# ext_bootload_activation.net
KiCad netlist of a schematic drawn in Altium Designer
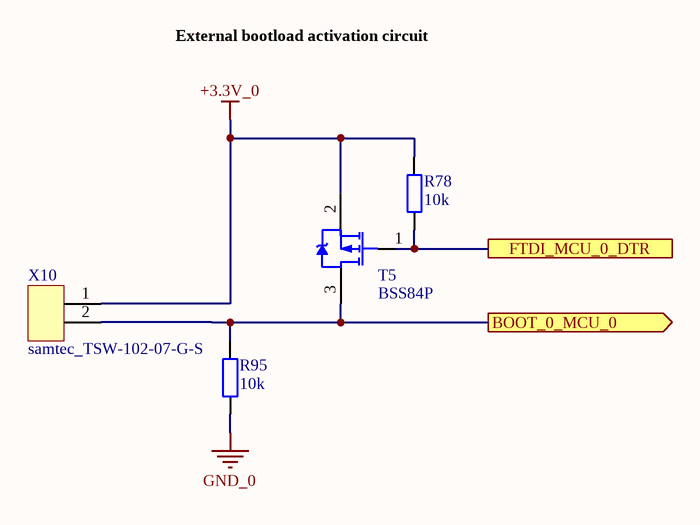
[diagram p0: ext_bootload_activation.SchDoc]

(export (version "E")
  (design (tool "Eeschema 10.0.6"))
  (components
    (comp (ref "R78")
      (value "10k")
      (footprint "0603R")
      (description "SMD Resistor 10k 0603")
      (fields (field (name "PART NUMBER") "gen_R_10k_0603") (field (name "TOLERANCE") "1%"))
      (libsource (lib "master-010106") (part "R"))
    )
    (comp (ref "R95")
      (value "10k")
      (footprint "0603R")
      (description "SMD Resistor 10k 0603")
      (fields (field (name "PART NUMBER") "gen_R_10k_0603") (field (name "TOLERANCE") "1%"))
      (libsource (lib "master-010106") (part "R"))
    )
    (comp (ref "T5")
      (value "BSS84P")
      (footprint "INF-PG-SOT23_N")
      (fields (field (name "MANUFACTURER") "Infineon"))
      (libsource (lib "Altium Content Vault") (part "INF-PEMOS-GSD-3-B"))
    )
    (comp (ref "X10")
      (value "samtec_TSW-102-07-G-S")
      (footprint "Pinheader_2.54_2")
      (description "Board-To-Board Connector, Vertical, 2.54 mm, 2 Contacts, Header, TSW Series, Through Hole, 1 Row")
      (fields (field (name "MANUFACTURER") "Samtec"))
      (libsource (lib "OE750") (part "X2"))
    )
  )
  (nets
    (net (code "1") (name "+3.3V_0") (class "Default")
      (node (ref "R78") (pin "2") (pinfunction "2_2") (pintype "passive"))
      (node (ref "T5") (pin "2") (pinfunction "SOURCE_2") (pintype "passive"))
      (node (ref "X10") (pin "1") (pintype "passive"))
    )
    (net (code "2") (name "/BOOT_0_MCU_0") (class "Default")
      (node (ref "R95") (pin "2") (pinfunction "2_2") (pintype "passive"))
      (node (ref "T5") (pin "3") (pinfunction "DRAIN_3") (pintype "passive"))
      (node (ref "X10") (pin "2") (pintype "passive"))
    )
    (net (code "3") (name "/FTDI_MCU_0_DTR") (class "Default")
      (node (ref "R78") (pin "1") (pinfunction "1_1") (pintype "passive"))
      (node (ref "T5") (pin "1") (pinfunction "GATE_1") (pintype "passive"))
    )
    (net (code "4") (name "GND_0") (class "Default")
      (node (ref "R95") (pin "1") (pinfunction "1_1") (pintype "passive"))
    )
  )
)
